# SCH_BMS.net
KiCad netlist of a schematic drawn in Altium Designer
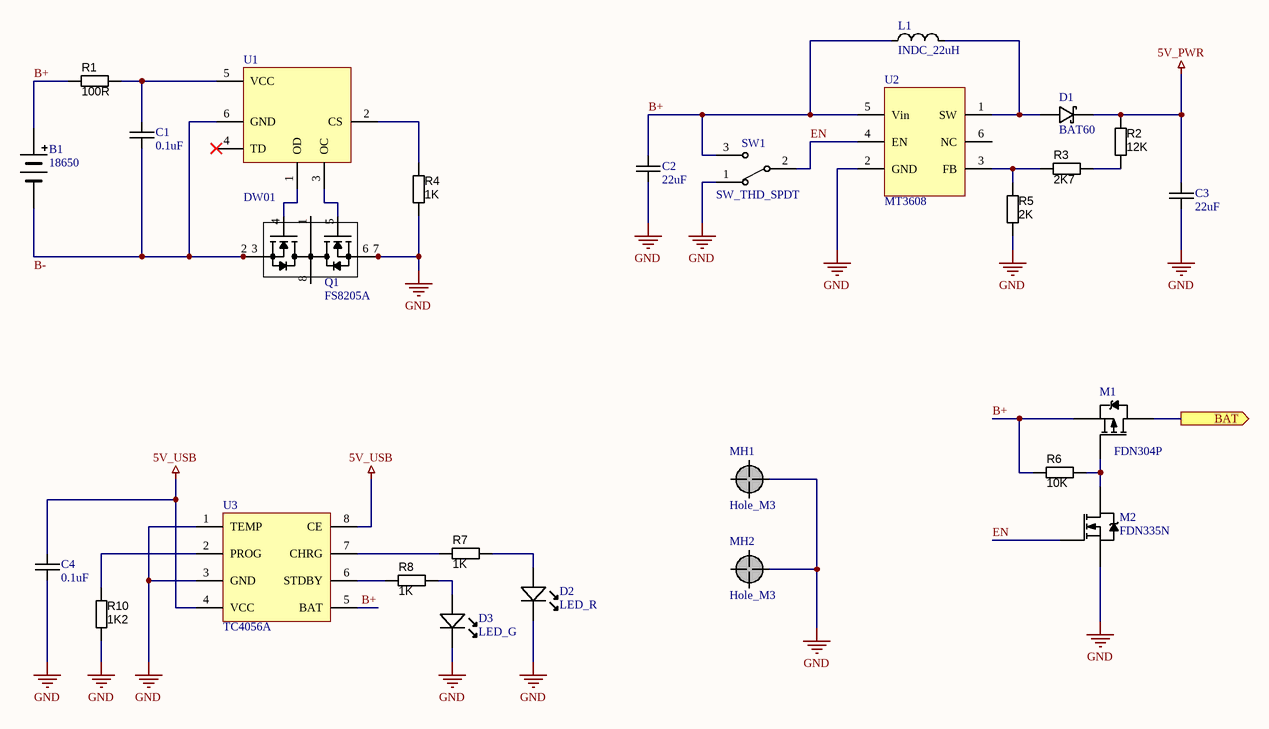
[diagram p0: SCH_BMS.SchDoc]

(export (version "E")
  (design (tool "Eeschema 10.0.6"))
  (components
    (comp (ref "B1")
      (value "18650")
      (footprint "BAT_18650")
      (libsource (lib "SchLib_AirMeter") (part "Battery_18650"))
    )
    (comp (ref "C1")
      (value "0.1uF")
      (footprint "CAP_0805")
      (description "SMD 0805")
      (libsource (lib "SchLib_AirMeter") (part "CAP_0.1uF"))
    )
    (comp (ref "C2")
      (value "22uF")
      (footprint "CAP_1206")
      (description "SMD 1206")
      (libsource (lib "SchLib_AirMeter") (part "CAP_22uF"))
    )
    (comp (ref "C3")
      (value "22uF")
      (footprint "CAP_1206")
      (description "SMD 1206")
      (libsource (lib "SchLib_AirMeter") (part "CAP_22uF"))
    )
    (comp (ref "C4")
      (value "0.1uF")
      (footprint "CAP_0805")
      (description "SMD 0805")
      (libsource (lib "SchLib_AirMeter") (part "CAP_0.1uF"))
    )
    (comp (ref "D1")
      (value "BAT60")
      (footprint "SOD323")
      (description "Schottky Diode 3A, Vf~0.24V, Vr=10V")
      (libsource (lib "SchLib_AirMeter") (part "BAT60"))
    )
    (comp (ref "D2")
      (value "LED_R")
      (footprint "LED_0805")
      (description "SMD_0805 2V")
      (libsource (lib "SchLib_AirMeter") (part "LED_R"))
    )
    (comp (ref "D3")
      (value "LED_G")
      (footprint "LED_0805")
      (description "SMD_0805 3V")
      (libsource (lib "SchLib_AirMeter") (part "LED_G"))
    )
    (comp (ref "L1")
      (value "INDC_22uH")
      (footprint "IND_10x10")
      (libsource (lib "SchLib_AirMeter") (part "INDC_22uH"))
    )
    (comp (ref "M1")
      (value "FDN304P")
      (footprint "SOT23_213")
      (libsource (lib "SchLib_AirMeter") (part "PMOS"))
    )
    (comp (ref "M2")
      (value "FDN335N")
      (footprint "SOT23_213")
      (libsource (lib "SchLib_AirMeter") (part "NMOS"))
    )
    (comp (ref "MH1")
      (value "Hole_M3")
      (footprint "Hole_M3")
      (libsource (lib "SchLib_AirMeter") (part "Hole_M3"))
    )
    (comp (ref "MH2")
      (value "Hole_M3")
      (footprint "Hole_M3")
      (libsource (lib "SchLib_AirMeter") (part "Hole_M3"))
    )
    (comp (ref "Q1")
      (value "FS8205A")
      (footprint "TSSOP65P640X120-8N")
      (description "NMOS, Drain-Connected, Imax 6A")
      (libsource (lib "SchLib_AirMeter") (part "FS8205A"))
    )
    (comp (ref "R1")
      (value "100R")
      (footprint "RESC3216X70N")
      (description "Resistor SMD, 1206")
      (libsource (lib "SchLib_AirMeter") (part "RES_100R"))
    )
    (comp (ref "R2")
      (value "12K")
      (footprint "RESC3216X70N")
      (description "Resistor SMD, 1206")
      (libsource (lib "SchLib_AirMeter") (part "RES_12K"))
    )
    (comp (ref "R3")
      (value "2K7")
      (footprint "RESC3216X70N")
      (description "Resistor SMD, 1206")
      (libsource (lib "SchLib_AirMeter") (part "RES_2K7"))
    )
    (comp (ref "R4")
      (value "1K")
      (footprint "RESC3216X70N")
      (description "Resistor SMD, 1206")
      (libsource (lib "") (part "RES_1K_1"))
    )
    (comp (ref "R5")
      (value "2K")
      (footprint "RESC3216X70N")
      (description "Resistor SMD, 1206")
      (libsource (lib "SchLib_AirMeter") (part "RES_2K"))
    )
    (comp (ref "R6")
      (value "10K")
      (footprint "RESC3216X70N")
      (description "Resistor SMD, 1206")
      (libsource (lib "SchLib_AirMeter") (part "RES_10K"))
    )
    (comp (ref "R7")
      (value "1K")
      (footprint "RESC3216X70N")
      (description "Resistor SMD, 1206")
      (libsource (lib "SchLib_AirMeter") (part "RES_1K"))
    )
    (comp (ref "R8")
      (value "1K")
      (footprint "RESC3216X70N")
      (description "Resistor SMD, 1206")
      (libsource (lib "SchLib_AirMeter") (part "RES_1K"))
    )
    (comp (ref "R10")
      (value "1K2")
      (footprint "RESC3216X70N")
      (description "Resistor SMD, 1206")
      (libsource (lib "SchLib_AirMeter") (part "RES_1K2"))
    )
    (comp (ref "SW1")
      (value "SW_THD_SPDT")
      (footprint "3P_header")
      (description "Switch 2 position")
      (libsource (lib "SchLib_AirMeter") (part "SW_THD_SPDT"))
    )
    (comp (ref "U1") (value "DW01") (footprint "SOT23-6") (libsource (lib "SchLib_AirMeter") (part "DW01")))
    (comp (ref "U2")
      (value "MT3608")
      (footprint "SOT23-6")
      (description "Boost Converter")
      (libsource (lib "SchLib_AirMeter") (part "MT3608"))
    )
    (comp (ref "U3")
      (value "TC4056A")
      (footprint "SOIC127P600X175-8AN")
      (libsource (lib "SchLib_AirMeter") (part "TC4056A"))
    )
  )
  (nets
    (net (code "1") (name "/B+") (class "Default")
      (node (ref "B1") (pin "1") (pinfunction "B+_1") (pintype "power_in"))
      (node (ref "C2") (pin "1") (pintype "passive"))
      (node (ref "L1") (pin "1") (pinfunction "1_1") (pintype "passive"))
      (node (ref "M1") (pin "2") (pinfunction "S_2") (pintype "passive"))
      (node (ref "R1") (pin "1") (pinfunction "1_1") (pintype "passive"))
      (node (ref "R6") (pin "1") (pinfunction "1_1") (pintype "passive"))
      (node (ref "SW1") (pin "3") (pinfunction "3_3") (pintype "passive"))
      (node (ref "U2") (pin "5") (pinfunction "Vin_5") (pintype "power_in"))
      (node (ref "U3") (pin "5") (pinfunction "BAT_5") (pintype "power_in"))
    )
    (net (code "2") (name "/B-") (class "Default")
      (node (ref "B1") (pin "2") (pinfunction "B+_2") (pintype "power_in"))
      (node (ref "C1") (pin "2") (pintype "passive"))
      (node (ref "Q1") (pin "2") (pinfunction "S1_2") (pintype "passive"))
      (node (ref "Q1") (pin "3") (pinfunction "S1_3") (pintype "passive"))
      (node (ref "U1") (pin "6") (pinfunction "GND_6") (pintype "power_in"))
    )
    (net (code "3") (name "/BAT") (class "Default")
      (node (ref "M1") (pin "3") (pinfunction "D_3") (pintype "passive"))
    )
    (net (code "4") (name "/EN") (class "Default")
      (node (ref "M2") (pin "1") (pinfunction "G_1") (pintype "passive"))
      (node (ref "SW1") (pin "2") (pinfunction "2_2") (pintype "passive"))
      (node (ref "U2") (pin "4") (pinfunction "EN_4") (pintype "power_in"))
    )
    (net (code "5") (name "5V_PWR") (class "Default")
      (node (ref "C3") (pin "1") (pintype "passive"))
      (node (ref "D1") (pin "K") (pinfunction "K_K") (pintype "passive"))
      (node (ref "R2") (pin "1") (pinfunction "1_1") (pintype "passive"))
    )
    (net (code "6") (name "5V_USB") (class "Default")
      (node (ref "C4") (pin "1") (pintype "passive"))
      (node (ref "U3") (pin "4") (pinfunction "VCC_4") (pintype "power_in"))
      (node (ref "U3") (pin "8") (pinfunction "CE_8") (pintype "power_in"))
    )
    (net (code "7") (name "GND") (class "Default")
      (node (ref "C2") (pin "2") (pintype "passive"))
      (node (ref "C3") (pin "2") (pintype "passive"))
      (node (ref "C4") (pin "2") (pintype "passive"))
      (node (ref "D2") (pin "K") (pinfunction "K_K") (pintype "passive"))
      (node (ref "D3") (pin "K") (pinfunction "K_K") (pintype "passive"))
      (node (ref "M2") (pin "2") (pinfunction "S_2") (pintype "passive"))
      (node (ref "MH1") (pin "MH") (pinfunction "MH_MH") (pintype "passive"))
      (node (ref "MH2") (pin "MH") (pinfunction "MH_MH") (pintype "passive"))
      (node (ref "Q1") (pin "6") (pinfunction "S1_6") (pintype "passive"))
      (node (ref "Q1") (pin "7") (pinfunction "S1_7") (pintype "passive"))
      (node (ref "R10") (pin "2") (pinfunction "2_2") (pintype "passive"))
      (node (ref "R4") (pin "2") (pinfunction "2_2") (pintype "passive"))
      (node (ref "R5") (pin "1") (pinfunction "1_1") (pintype "passive"))
      (node (ref "SW1") (pin "1") (pinfunction "1_1") (pintype "passive"))
      (node (ref "U2") (pin "2") (pinfunction "GND_2") (pintype "power_in"))
      (node (ref "U3") (pin "1") (pinfunction "TEMP_1") (pintype "power_in"))
      (node (ref "U3") (pin "3") (pinfunction "GND_3") (pintype "power_in"))
    )
    (net (code "8") (name "Net-(D2-PadA)") (class "Default")
      (node (ref "D2") (pin "A") (pinfunction "A_A") (pintype "passive"))
      (node (ref "R7") (pin "2") (pinfunction "2_2") (pintype "passive"))
    )
    (net (code "9") (name "Net-(D3-PadA)") (class "Default")
      (node (ref "D3") (pin "A") (pinfunction "A_A") (pintype "passive"))
      (node (ref "R8") (pin "2") (pinfunction "2_2") (pintype "passive"))
    )
    (net (code "10") (name "Net-(M1-G)") (class "Default")
      (node (ref "M1") (pin "1") (pinfunction "G_1") (pintype "passive"))
      (node (ref "M2") (pin "3") (pinfunction "D_3") (pintype "passive"))
      (node (ref "R6") (pin "2") (pinfunction "2_2") (pintype "passive"))
    )
    (net (code "11") (name "Net-(Q1-G1)") (class "Default")
      (node (ref "Q1") (pin "4") (pinfunction "G1_4") (pintype "passive"))
      (node (ref "U1") (pin "1") (pinfunction "OD_1") (pintype "power_in"))
    )
    (net (code "12") (name "Net-(Q1-G2)") (class "Default")
      (node (ref "Q1") (pin "5") (pinfunction "G2_5") (pintype "passive"))
      (node (ref "U1") (pin "3") (pinfunction "OC_3") (pintype "power_in"))
    )
    (net (code "13") (name "Net-(R2-Pad2)") (class "Default")
      (node (ref "R2") (pin "2") (pinfunction "2_2") (pintype "passive"))
      (node (ref "R3") (pin "2") (pinfunction "2_2") (pintype "passive"))
    )
    (net (code "14") (name "Net-(U1-CS)") (class "Default")
      (node (ref "R4") (pin "1") (pinfunction "1_1") (pintype "passive"))
      (node (ref "U1") (pin "2") (pinfunction "CS_2") (pintype "power_in"))
    )
    (net (code "15") (name "Net-(U1-VCC)") (class "Default")
      (node (ref "C1") (pin "1") (pintype "passive"))
      (node (ref "R1") (pin "2") (pinfunction "2_2") (pintype "passive"))
      (node (ref "U1") (pin "5") (pinfunction "VCC_5") (pintype "power_in"))
    )
    (net (code "16") (name "Net-(U2-FB)") (class "Default")
      (node (ref "R3") (pin "1") (pinfunction "1_1") (pintype "passive"))
      (node (ref "R5") (pin "2") (pinfunction "2_2") (pintype "passive"))
      (node (ref "U2") (pin "3") (pinfunction "FB_3") (pintype "power_in"))
    )
    (net (code "17") (name "Net-(U2-SW)") (class "Default")
      (node (ref "D1") (pin "A") (pinfunction "A_A") (pintype "passive"))
      (node (ref "L1") (pin "2") (pinfunction "2_2") (pintype "passive"))
      (node (ref "U2") (pin "1") (pinfunction "SW_1") (pintype "power_in"))
    )
    (net (code "18") (name "Net-(U3-CHRG)") (class "Default")
      (node (ref "R7") (pin "1") (pinfunction "1_1") (pintype "passive"))
      (node (ref "U3") (pin "7") (pinfunction "CHRG_7") (pintype "power_in"))
    )
    (net (code "19") (name "Net-(U3-PROG)") (class "Default")
      (node (ref "R10") (pin "1") (pinfunction "1_1") (pintype "passive"))
      (node (ref "U3") (pin "2") (pinfunction "PROG_2") (pintype "passive"))
    )
    (net (code "20") (name "Net-(U3-STDBY)") (class "Default")
      (node (ref "R8") (pin "1") (pinfunction "1_1") (pintype "passive"))
      (node (ref "U3") (pin "6") (pinfunction "STDBY_6") (pintype "power_in"))
    )
    (net (code "21") (name "unconnected-(Q1-D12-Pad1)") (class "Default")
      (node (ref "Q1") (pin "1") (pinfunction "D12_1") (pintype "passive"))
    )
    (net (code "22") (name "unconnected-(Q1-D12-Pad8)") (class "Default")
      (node (ref "Q1") (pin "8") (pinfunction "D12_8") (pintype "passive"))
    )
    (net (code "23") (name "unconnected-(U1-TD-Pad4)") (class "Default")
      (node (ref "U1") (pin "4") (pinfunction "TD_4") (pintype "power_in+no_connect"))
    )
    (net (code "24") (name "unconnected-(U2-NC-Pad6)") (class "Default")
      (node (ref "U2") (pin "6") (pinfunction "NC_6") (pintype "power_in"))
    )
  )
)
